# Power.net
KiCad netlist of a schematic drawn in Altium Designer
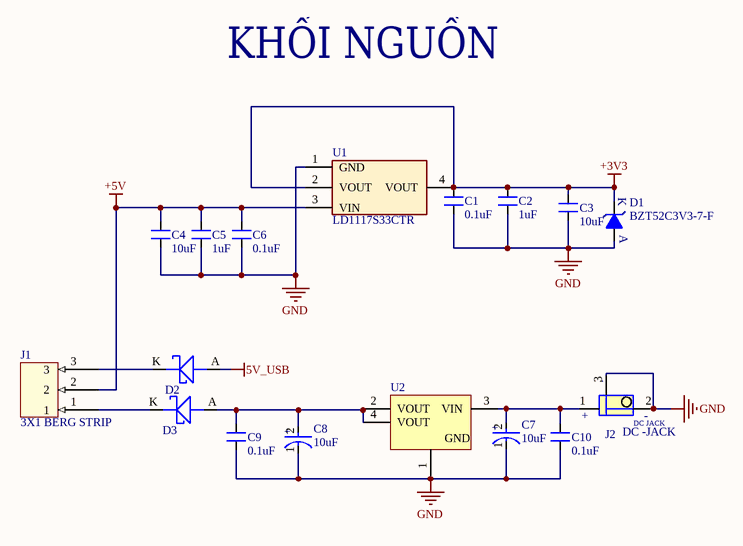
[diagram p0: Power.SchDoc]

(export (version "E")
  (design (tool "Eeschema 10.0.6"))
  (components
    (comp (ref "C1")
      (value "0.1uF")
      (footprint "CAP_0805")
      (description "0.1µF ±10% 50V Ceramic Capacitor X7R 0805 (2012 Metric)")
      (fields
        (field (name "MANUFACTURER") "Samsung")
        (field (name "MANUFACTURER PART NUMBER") "CL21B104KBCNNNC")
      )
      (libsource (lib "ESTEEMPCBLIB") (part "CAP_0.1uF-50V-10%-0805"))
    )
    (comp (ref "C2")
      (value "1uF")
      (footprint "CAP_0805")
      (description "1µF ±5% 50V Ceramic Capacitor X7R 0805 (2012 Metric)")
      (fields
        (field (name "MANUFACTURER") "Samsung")
        (field (name "MANUFACTURER PART NUMBER") "CC0805JKX7R9BB105")
      )
      (libsource (lib "ESTEEMPCBLIB") (part "CAP_1uF-50V-5%-0805"))
    )
    (comp (ref "C3")
      (value "10uF")
      (footprint "CAP_1206")
      (description "10µF ±10% 50V Ceramic Capacitor X7R 1206 (3216 Metric)")
      (fields
        (field (name "MANUFACTURER") "KEMET")
        (field (name "MANUFACTURER PART NUMBER") "CL31B106KBHNNNE")
      )
      (libsource (lib "ESTEEMPCBLIB") (part "CAP_10uF-50V-10%-1206"))
    )
    (comp (ref "C4")
      (value "10uF")
      (footprint "CAP_1206")
      (description "10µF ±10% 50V Ceramic Capacitor X7R 1206 (3216 Metric)")
      (fields
        (field (name "MANUFACTURER") "KEMET")
        (field (name "MANUFACTURER PART NUMBER") "CL31B106KBHNNNE")
      )
      (libsource (lib "ESTEEMPCBLIB") (part "CAP_10uF-50V-10%-1206"))
    )
    (comp (ref "C5")
      (value "1uF")
      (footprint "CAP_0805")
      (description "1µF ±5% 50V Ceramic Capacitor X7R 0805 (2012 Metric)")
      (fields
        (field (name "MANUFACTURER") "Samsung")
        (field (name "MANUFACTURER PART NUMBER") "CC0805JKX7R9BB105")
      )
      (libsource (lib "ESTEEMPCBLIB") (part "CAP_1uF-50V-5%-0805"))
    )
    (comp (ref "C6")
      (value "0.1uF")
      (footprint "CAP_0805")
      (description "0.1µF ±10% 50V Ceramic Capacitor X7R 0805 (2012 Metric)")
      (fields
        (field (name "MANUFACTURER") "Samsung")
        (field (name "MANUFACTURER PART NUMBER") "CL21B104KBCNNNC")
      )
      (libsource (lib "ESTEEMPCBLIB") (part "CAP_0.1uF-50V-10%-0805"))
    )
    (comp (ref "C7")
      (value "10uF")
      (footprint "FP-293DA-MFG")
      (fields (field (name "TOLERANCE") "20%"))
      (libsource (lib "Altium Content Vault") (part "a00bbbee19879c290e62620ae7e47b1"))
    )
    (comp (ref "C8")
      (value "10uF")
      (footprint "FP-293DA-MFG")
      (fields (field (name "TOLERANCE") "20%"))
      (libsource (lib "Altium Content Vault") (part "a00bbbee19879c290e62620ae7e47b1"))
    )
    (comp (ref "C9")
      (value "0.1uF")
      (footprint "CAP_0805")
      (description "0.1µF ±10% 50V Ceramic Capacitor X7R 0805 (2012 Metric)")
      (fields
        (field (name "MANUFACTURER") "Samsung")
        (field (name "MANUFACTURER PART NUMBER") "CL21B104KBCNNNC")
      )
      (libsource (lib "ESTEEMPCBLIB") (part "CAP_0.1uF-50V-10%-0805"))
    )
    (comp (ref "C10")
      (value "0.1uF")
      (footprint "CAP_0805")
      (description "0.1µF ±10% 50V Ceramic Capacitor X7R 0805 (2012 Metric)")
      (fields
        (field (name "MANUFACTURER") "Samsung")
        (field (name "MANUFACTURER PART NUMBER") "CL21B104KBCNNNC")
      )
      (libsource (lib "ESTEEMPCBLIB") (part "CAP_0.1uF-50V-10%-0805"))
    )
    (comp (ref "D1")
      (value "BZT52C3V3-7-F")
      (footprint "DIO_SOD-123")
      (description "Zener Diode 3.3V 500mW ±6% Surface Mount SOD-123")
      (fields (field (name "MANUFACTURER") "Diodes Incorporated"))
      (libsource (lib "ESTEEMPCBLIB") (part "DIO-Z_3.3V-500mW-SOD123"))
    )
    (comp (ref "D2")
      (value "MBRS130LT3G")
      (footprint "DIO_SMB_DO-214AA")
      (description "Diode Schottky 30V 2A Surface Mount SMB")
      (fields (field (name "MANUFACTURER") "ON Semiconductor"))
      (libsource (lib "ESTEEMPCBLIB") (part "DIO-S_445mV-30V-2A-SMB"))
    )
    (comp (ref "D3")
      (value "MBRS130LT3G")
      (footprint "DIO_SMB_DO-214AA")
      (description "Diode Schottky 30V 2A Surface Mount SMB")
      (fields (field (name "MANUFACTURER") "ON Semiconductor"))
      (libsource (lib "ESTEEMPCBLIB") (part "DIO-S_445mV-30V-2A-SMB"))
    )
    (comp (ref "J1")
      (value "3X1 BERG STRIP")
      (footprint "CON3_100_40D72_TH_ST-MALE")
      (description "3 Pins, 1 Row 2.54mm Pitch, Straight bergstrip, Male")
      (fields (field (name "MANUFACTURER PART NUMBER") "RKI-1140") (field (name "MANUFACTURER") "NA"))
      (libsource (lib "ESTEEMPCBLIB") (part "CON-BS-PLG_3X1-100-ST-TH"))
    )
    (comp (ref "J2")
      (value "DC -JACK")
      (footprint "CON3_129_PJ-002A_TH_RA")
      (description "3 Pins, 1 Row 228mil Pitch, right angle Connector, male")
      (fields (field (name "MANUFACTURER") "JST") (field (name "MANUFACTURER PART NUMBER") "PJ-002A"))
      (libsource (lib "ESTEEMPCBLIB") (part "CON-PLG_3X1-228-DC_JACK"))
    )
    (comp (ref "U1")
      (value "LD1117S33CTR")
      (footprint "SOT223_3")
      (description "Linear Voltage Regulator IC 1 Output 800mA SOT-223")
      (fields (field (name "MANUFACTURER") "STMicroelectronics"))
      (libsource (lib "ESTEEMPCBLIB") (part "REG_15V-3.3V-0.9A-12W-SOT223"))
    )
    (comp (ref "U2")
      (value "LD1117S50CTR")
      (footprint "SOT-223_N")
      (description "Fixed Low Drop Positive Voltage Regulator, 5V, 4-Pin SOT-223, Tape and Reel")
      (libsource (lib "Altium Content Vault") (part "PM-REG-LD1117-SOT4"))
    )
  )
  (nets
    (net (code "1") (name "+3V3") (class "Default")
      (node (ref "C1") (pin "2") (pinfunction "2_2") (pintype "passive"))
      (node (ref "C2") (pin "2") (pinfunction "2_2") (pintype "passive"))
      (node (ref "C3") (pin "2") (pinfunction "2_2") (pintype "passive"))
      (node (ref "D1") (pin "K") (pinfunction "K_K") (pintype "passive"))
      (node (ref "U1") (pin "2") (pinfunction "VOUT_2") (pintype "passive"))
      (node (ref "U1") (pin "4") (pinfunction "VOUT_4") (pintype "passive"))
    )
    (net (code "2") (name "+5V") (class "Default")
      (node (ref "C4") (pin "2") (pinfunction "2_2") (pintype "passive"))
      (node (ref "C5") (pin "2") (pinfunction "2_2") (pintype "passive"))
      (node (ref "C6") (pin "2") (pinfunction "2_2") (pintype "passive"))
      (node (ref "J1") (pin "2") (pinfunction "2_2") (pintype "input"))
      (node (ref "U1") (pin "3") (pinfunction "VIN_3") (pintype "passive"))
    )
    (net (code "3") (name "5V_USB") (class "Default")
      (node (ref "D2") (pin "A") (pinfunction "A_A") (pintype "passive"))
    )
    (net (code "4") (name "GND") (class "Default")
      (node (ref "C1") (pin "1") (pinfunction "1_1") (pintype "passive"))
      (node (ref "C10") (pin "1") (pinfunction "1_1") (pintype "passive"))
      (node (ref "C2") (pin "1") (pinfunction "1_1") (pintype "passive"))
      (node (ref "C3") (pin "1") (pinfunction "1_1") (pintype "passive"))
      (node (ref "C4") (pin "1") (pinfunction "1_1") (pintype "passive"))
      (node (ref "C5") (pin "1") (pinfunction "1_1") (pintype "passive"))
      (node (ref "C6") (pin "1") (pinfunction "1_1") (pintype "passive"))
      (node (ref "C7") (pin "1") (pinfunction "C_1") (pintype "passive"))
      (node (ref "C8") (pin "1") (pinfunction "C_1") (pintype "passive"))
      (node (ref "C9") (pin "1") (pinfunction "1_1") (pintype "passive"))
      (node (ref "D1") (pin "A") (pinfunction "A_A") (pintype "passive"))
      (node (ref "J2") (pin "2") (pinfunction "2_2") (pintype "passive"))
      (node (ref "J2") (pin "3") (pinfunction "-_3") (pintype "passive"))
      (node (ref "U1") (pin "1") (pinfunction "GND_1") (pintype "passive"))
      (node (ref "U2") (pin "1") (pinfunction "GND_1") (pintype "passive"))
    )
    (net (code "5") (name "Net-(C7-A)") (class "Default")
      (node (ref "C10") (pin "2") (pinfunction "2_2") (pintype "passive"))
      (node (ref "C7") (pin "2") (pinfunction "A_2") (pintype "passive"))
      (node (ref "J2") (pin "1") (pinfunction "1_1") (pintype "passive"))
      (node (ref "U2") (pin "3") (pinfunction "VIN_3") (pintype "power_in"))
    )
    (net (code "6") (name "Net-(C8-A)") (class "Default")
      (node (ref "C8") (pin "2") (pinfunction "A_2") (pintype "passive"))
      (node (ref "C9") (pin "2") (pinfunction "2_2") (pintype "passive"))
      (node (ref "D3") (pin "A") (pinfunction "A_A") (pintype "passive"))
      (node (ref "U2") (pin "2") (pinfunction "VOUT_2") (pintype "power_in"))
      (node (ref "U2") (pin "4") (pinfunction "VOUT_4") (pintype "power_in"))
    )
    (net (code "7") (name "Net-(D2-PadK)") (class "Default")
      (node (ref "D2") (pin "K") (pinfunction "K_K") (pintype "passive"))
      (node (ref "J1") (pin "3") (pinfunction "3_3") (pintype "input"))
    )
    (net (code "8") (name "Net-(D3-PadK)") (class "Default")
      (node (ref "D3") (pin "K") (pinfunction "K_K") (pintype "passive"))
      (node (ref "J1") (pin "1") (pinfunction "1_1") (pintype "input"))
    )
  )
)
